# CurlingStoneSchematic.net
KiCad netlist of a schematic drawn in Altium Designer
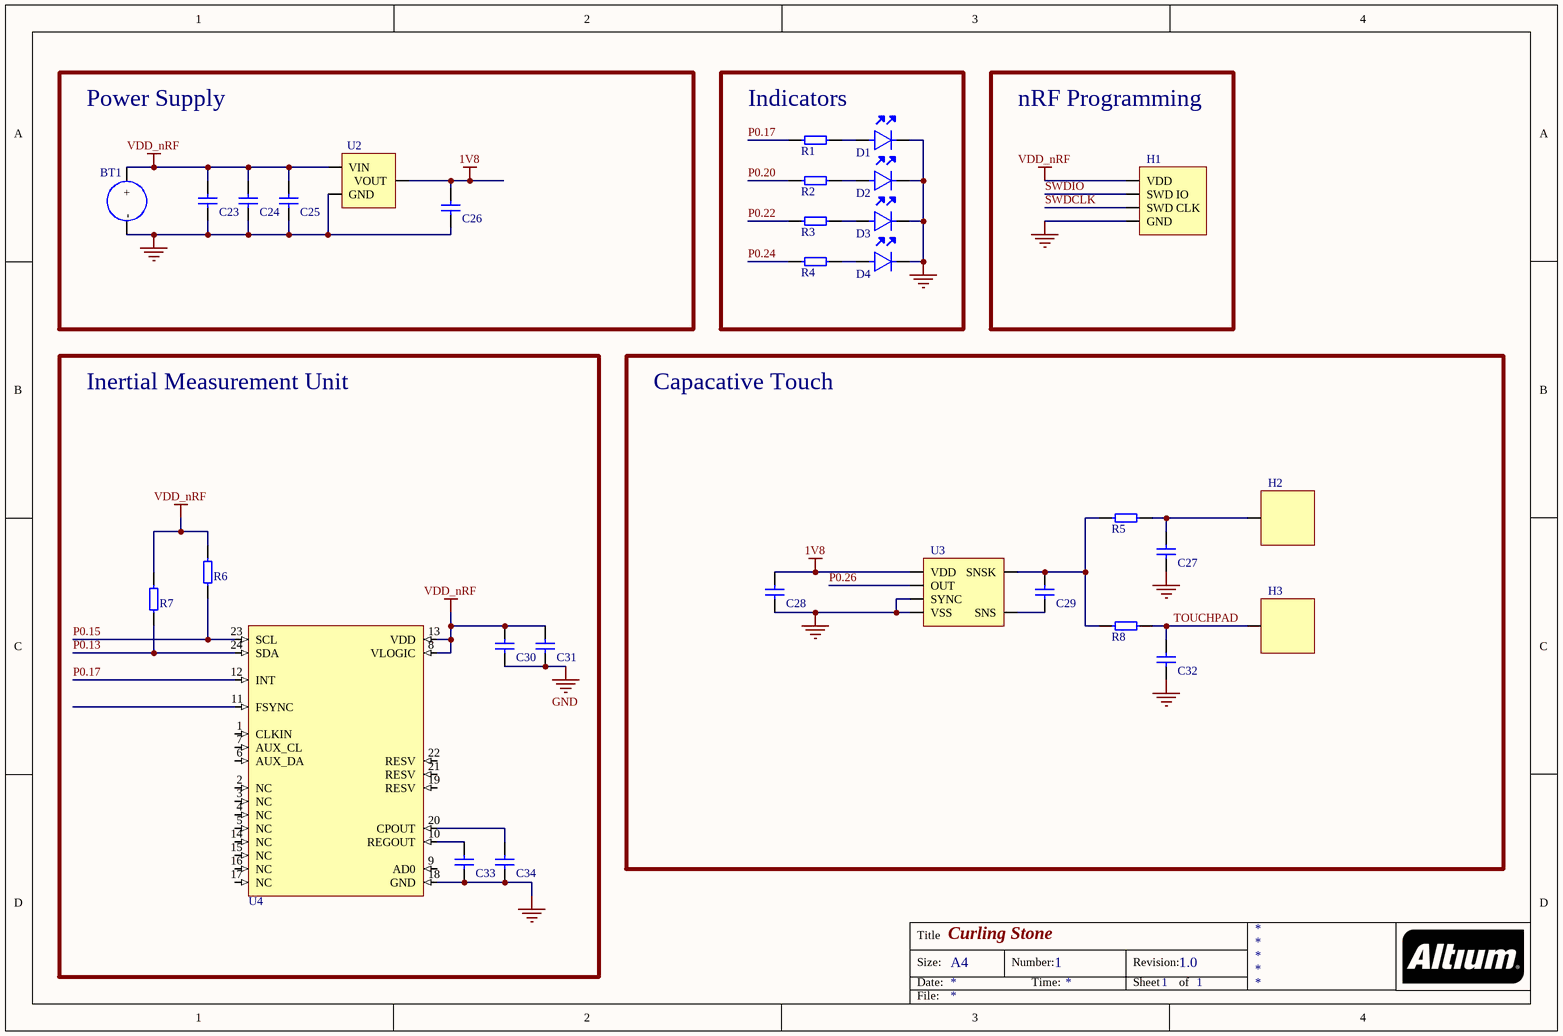
[diagram p0: CurlingStoneSchematic.SchDoc]

(export (version "E")
  (design (tool "Eeschema 10.0.6"))
  (components
    (comp (ref "BT1")
      (value "Battery Holder")
      (footprint "Battery Holder")
      (description "Battery Holder 1-Cell 20mm Size Tin Nickel SMT Mount T/R")
      (libsource (lib "ElsysSchematicLibrary") (part "Battery Holder"))
    )
    (comp (ref "C23")
      (value "0603 Capacitor")
      (footprint "0603")
      (libsource (lib "CurlingStoneSchematicLibrary") (part "0603 Capacitor"))
    )
    (comp (ref "C24")
      (value "0603 Capacitor")
      (footprint "0603")
      (libsource (lib "CurlingStoneSchematicLibrary") (part "0603 Capacitor"))
    )
    (comp (ref "C25")
      (value "0603 Capacitor")
      (footprint "0603")
      (libsource (lib "CurlingStoneSchematicLibrary") (part "0603 Capacitor"))
    )
    (comp (ref "C26")
      (value "0603 Capacitor")
      (footprint "0603")
      (libsource (lib "CurlingStoneSchematicLibrary") (part "0603 Capacitor"))
    )
    (comp (ref "C27")
      (value "0603 Capacitor")
      (footprint "0603")
      (libsource (lib "CurlingStoneSchematicLibrary") (part "0603 Capacitor"))
    )
    (comp (ref "C28")
      (value "0603 Capacitor")
      (footprint "0603")
      (libsource (lib "CurlingStoneSchematicLibrary") (part "0603 Capacitor"))
    )
    (comp (ref "C29")
      (value "0603 Capacitor")
      (footprint "0603")
      (libsource (lib "CurlingStoneSchematicLibrary") (part "0603 Capacitor"))
    )
    (comp (ref "C30")
      (value "0603 Capacitor")
      (footprint "0603")
      (libsource (lib "CurlingStoneSchematicLibrary") (part "0603 Capacitor"))
    )
    (comp (ref "C31")
      (value "0603 Capacitor")
      (footprint "0603")
      (libsource (lib "CurlingStoneSchematicLibrary") (part "0603 Capacitor"))
    )
    (comp (ref "C32")
      (value "0603 Capacitor")
      (footprint "0603")
      (libsource (lib "CurlingStoneSchematicLibrary") (part "0603 Capacitor"))
    )
    (comp (ref "C33")
      (value "0603 Capacitor")
      (footprint "0603")
      (libsource (lib "CurlingStoneSchematicLibrary") (part "0603 Capacitor"))
    )
    (comp (ref "C34")
      (value "0603 Capacitor")
      (footprint "0603")
      (libsource (lib "CurlingStoneSchematicLibrary") (part "0603 Capacitor"))
    )
    (comp (ref "D1")
      (value "0603 LED")
      (footprint "0603 LED")
      (description "LED Uni-Color Green 574nm 2-Pin Chip LED T/R")
      (libsource (lib "CurlingStoneSchematicLibrary") (part "0603 LED"))
    )
    (comp (ref "D2")
      (value "0603 LED")
      (footprint "0603 LED")
      (description "LED Uni-Color Green 574nm 2-Pin Chip LED T/R")
      (libsource (lib "CurlingStoneSchematicLibrary") (part "0603 LED"))
    )
    (comp (ref "D3")
      (value "0603 LED")
      (footprint "0603 LED")
      (description "LED Uni-Color Green 574nm 2-Pin Chip LED T/R")
      (libsource (lib "CurlingStoneSchematicLibrary") (part "0603 LED"))
    )
    (comp (ref "D4")
      (value "0603 LED")
      (footprint "0603 LED")
      (description "LED Uni-Color Green 574nm 2-Pin Chip LED T/R")
      (libsource (lib "CurlingStoneSchematicLibrary") (part "0603 LED"))
    )
    (comp (ref "H1")
      (value "4x1 Header")
      (footprint "4x1 HEADER TH")
      (libsource (lib "ElsysSchematicLibrary") (part "4x1 Header"))
    )
    (comp (ref "H2")
      (value "Electrode")
      (footprint "ELECTRODE EXTERNAL")
      (libsource (lib "CurlingStoneSchematicLibrary") (part "Electrode"))
    )
    (comp (ref "H3")
      (value "Electrode")
      (footprint "ELECTRODE INTERNAL")
      (libsource (lib "CurlingStoneSchematicLibrary") (part "Electrode"))
    )
    (comp (ref "R1")
      (value "0603 Resistor")
      (footprint "0603")
      (libsource (lib "CurlingStoneSchematicLibrary") (part "0603 Resistor"))
    )
    (comp (ref "R2")
      (value "0603 Resistor")
      (footprint "0603")
      (libsource (lib "CurlingStoneSchematicLibrary") (part "0603 Resistor"))
    )
    (comp (ref "R3")
      (value "0603 Resistor")
      (footprint "0603")
      (libsource (lib "CurlingStoneSchematicLibrary") (part "0603 Resistor"))
    )
    (comp (ref "R4")
      (value "0603 Resistor")
      (footprint "0603")
      (libsource (lib "CurlingStoneSchematicLibrary") (part "0603 Resistor"))
    )
    (comp (ref "R5")
      (value "0603 Resistor")
      (footprint "0603")
      (libsource (lib "CurlingStoneSchematicLibrary") (part "0603 Resistor"))
    )
    (comp (ref "R6")
      (value "0603 Resistor")
      (footprint "0603")
      (libsource (lib "CurlingStoneSchematicLibrary") (part "0603 Resistor"))
    )
    (comp (ref "R7")
      (value "0603 Resistor")
      (footprint "0603")
      (libsource (lib "CurlingStoneSchematicLibrary") (part "0603 Resistor"))
    )
    (comp (ref "R8")
      (value "0603 Resistor")
      (footprint "0603")
      (libsource (lib "CurlingStoneSchematicLibrary") (part "0603 Resistor"))
    )
    (comp (ref "U2")
      (value "MCP1700 1V8")
      (footprint "MCP1700 SOT-23")
      (libsource (lib "ElsysSchematicLibrary") (part "MCP1700 1V8"))
    )
    (comp (ref "U3")
      (value "Capacative Touch")
      (footprint "CAPACATIVE TOUCH")
      (description "Capacitive Touch Screen 1Keys 6-Pin SOT-23 Tape and Reel")
      (libsource (lib "CurlingStoneSchematicLibrary") (part "Capacative Touch"))
    )
    (comp (ref "U4")
      (value "MPU-6050")
      (footprint "MPU-6050")
      (description "INVENSENSE   MPU-6050   GYRO / ACCEL, 6-AXIS, I2C, QFN-24")
      (libsource (lib "CurlingStoneSchematicLibrary") (part "MPU-6050"))
    )
  )
  (nets
    (net (code "1") (name "/P0.13") (class "Default")
      (node (ref "R7") (pin "1") (pintype "passive"))
      (node (ref "U4") (pin "24") (pinfunction "SDA_24") (pintype "input"))
    )
    (net (code "2") (name "/P0.15") (class "Default")
      (node (ref "R6") (pin "1") (pintype "passive"))
      (node (ref "U4") (pin "23") (pinfunction "SCL_23") (pintype "input"))
    )
    (net (code "3") (name "/P0.17") (class "Default")
      (node (ref "R1") (pin "1") (pintype "passive"))
      (node (ref "U4") (pin "12") (pinfunction "INT_12") (pintype "input"))
    )
    (net (code "4") (name "/P0.20") (class "Default") (node (ref "R2") (pin "1") (pintype "passive")))
    (net (code "5") (name "/P0.22") (class "Default") (node (ref "R3") (pin "1") (pintype "passive")))
    (net (code "6") (name "/P0.24") (class "Default") (node (ref "R4") (pin "1") (pintype "passive")))
    (net (code "7") (name "/P0.26") (class "Default")
      (node (ref "U3") (pin "1") (pinfunction "OUT_1") (pintype "passive"))
    )
    (net (code "8") (name "/SWDCLK") (class "Default")
      (node (ref "H1") (pin "4") (pinfunction "SWD_CLK_4") (pintype "passive"))
    )
    (net (code "9") (name "/SWDIO") (class "Default")
      (node (ref "H1") (pin "3") (pinfunction "SWD_IO_3") (pintype "passive"))
    )
    (net (code "10") (name "/TOUCHPAD") (class "Default")
      (node (ref "C32") (pin "2") (pintype "passive"))
      (node (ref "H3") (pin "1") (pinfunction "GND_1") (pintype "passive"))
      (node (ref "R8") (pin "2") (pintype "passive"))
    )
    (net (code "11") (name "1V8") (class "Default")
      (node (ref "C26") (pin "2") (pintype "passive"))
      (node (ref "C28") (pin "2") (pintype "passive"))
      (node (ref "U2") (pin "2") (pinfunction "VOUT_2") (pintype "passive"))
      (node (ref "U3") (pin "5") (pinfunction "VDD_5") (pintype "passive"))
    )
    (net (code "12") (name "GND") (class "Default")
      (node (ref "BT1") (pin "2") (pinfunction "-_2") (pintype "passive"))
      (node (ref "C23") (pin "1") (pintype "passive"))
      (node (ref "C24") (pin "1") (pintype "passive"))
      (node (ref "C25") (pin "1") (pintype "passive"))
      (node (ref "C26") (pin "1") (pintype "passive"))
      (node (ref "C27") (pin "1") (pintype "passive"))
      (node (ref "C28") (pin "1") (pintype "passive"))
      (node (ref "C30") (pin "1") (pintype "passive"))
      (node (ref "C31") (pin "1") (pintype "passive"))
      (node (ref "C32") (pin "1") (pintype "passive"))
      (node (ref "C33") (pin "1") (pintype "passive"))
      (node (ref "C34") (pin "1") (pintype "passive"))
      (node (ref "D1") (pin "2") (pintype "passive"))
      (node (ref "D2") (pin "2") (pintype "passive"))
      (node (ref "D3") (pin "2") (pintype "passive"))
      (node (ref "D4") (pin "2") (pintype "passive"))
      (node (ref "H1") (pin "2") (pinfunction "GND_2") (pintype "passive"))
      (node (ref "U2") (pin "1") (pinfunction "GND_1") (pintype "passive"))
      (node (ref "U3") (pin "2") (pinfunction "VSS_2") (pintype "passive"))
      (node (ref "U3") (pin "6") (pinfunction "SYNC_6") (pintype "passive"))
      (node (ref "U4") (pin "18") (pinfunction "GND_18") (pintype "input"))
    )
    (net (code "13") (name "Net-(D1-Pad1)") (class "Default")
      (node (ref "D1") (pin "1") (pintype "passive"))
      (node (ref "R1") (pin "2") (pintype "passive"))
    )
    (net (code "14") (name "Net-(D2-Pad1)") (class "Default")
      (node (ref "D2") (pin "1") (pintype "passive"))
      (node (ref "R2") (pin "2") (pintype "passive"))
    )
    (net (code "15") (name "Net-(D3-Pad1)") (class "Default")
      (node (ref "D3") (pin "1") (pintype "passive"))
      (node (ref "R3") (pin "2") (pintype "passive"))
    )
    (net (code "16") (name "Net-(D4-Pad1)") (class "Default")
      (node (ref "D4") (pin "1") (pintype "passive"))
      (node (ref "R4") (pin "2") (pintype "passive"))
    )
    (net (code "17") (name "Net-(H2-GND)") (class "Default")
      (node (ref "C27") (pin "2") (pintype "passive"))
      (node (ref "H2") (pin "1") (pinfunction "GND_1") (pintype "passive"))
      (node (ref "R5") (pin "2") (pintype "passive"))
    )
    (net (code "18") (name "Net-(U3-SNS)") (class "Default")
      (node (ref "C29") (pin "1") (pintype "passive"))
      (node (ref "U3") (pin "4") (pinfunction "SNS_4") (pintype "passive"))
    )
    (net (code "19") (name "Net-(U3-SNSK)") (class "Default")
      (node (ref "C29") (pin "2") (pintype "passive"))
      (node (ref "R5") (pin "1") (pintype "passive"))
      (node (ref "R8") (pin "1") (pintype "passive"))
      (node (ref "U3") (pin "3") (pinfunction "SNSK_3") (pintype "passive"))
    )
    (net (code "20") (name "Net-(U4-CPOUT)") (class "Default")
      (node (ref "C34") (pin "2") (pintype "passive"))
      (node (ref "U4") (pin "20") (pinfunction "CPOUT_20") (pintype "input"))
    )
    (net (code "21") (name "Net-(U4-REGOUT)") (class "Default")
      (node (ref "C33") (pin "2") (pintype "passive"))
      (node (ref "U4") (pin "10") (pinfunction "REGOUT_10") (pintype "input"))
    )
    (net (code "22") (name "VDD_nRF") (class "Default")
      (node (ref "BT1") (pin "1") (pinfunction "+_1") (pintype "passive"))
      (node (ref "C23") (pin "2") (pintype "passive"))
      (node (ref "C24") (pin "2") (pintype "passive"))
      (node (ref "C25") (pin "2") (pintype "passive"))
      (node (ref "C30") (pin "2") (pintype "passive"))
      (node (ref "C31") (pin "2") (pintype "passive"))
      (node (ref "H1") (pin "1") (pinfunction "VDD_1") (pintype "passive"))
      (node (ref "R6") (pin "2") (pintype "passive"))
      (node (ref "R7") (pin "2") (pintype "passive"))
      (node (ref "U2") (pin "3") (pinfunction "VIN_3") (pintype "passive"))
      (node (ref "U4") (pin "13") (pinfunction "VDD_13") (pintype "input"))
      (node (ref "U4") (pin "8") (pinfunction "VLOGIC_8") (pintype "input"))
    )
    (net (code "23") (name "unconnected-(U4-AD0-Pad9)") (class "Default")
      (node (ref "U4") (pin "9") (pinfunction "AD0_9") (pintype "input"))
    )
    (net (code "24") (name "unconnected-(U4-AUX_CL-Pad7)") (class "Default")
      (node (ref "U4") (pin "7") (pinfunction "AUX_CL_7") (pintype "input"))
    )
    (net (code "25") (name "unconnected-(U4-AUX_DA-Pad6)") (class "Default")
      (node (ref "U4") (pin "6") (pinfunction "AUX_DA_6") (pintype "input"))
    )
    (net (code "26") (name "unconnected-(U4-CLKIN-Pad1)") (class "Default")
      (node (ref "U4") (pin "1") (pinfunction "CLKIN_1") (pintype "input"))
    )
    (net (code "27") (name "unconnected-(U4-FSYNC-Pad11)") (class "Default")
      (node (ref "U4") (pin "11") (pinfunction "FSYNC_11") (pintype "input"))
    )
    (net (code "28") (name "unconnected-(U4-NC-Pad2)") (class "Default")
      (node (ref "U4") (pin "2") (pinfunction "NC_2") (pintype "input"))
    )
    (net (code "29") (name "unconnected-(U4-NC-Pad3)") (class "Default")
      (node (ref "U4") (pin "3") (pinfunction "NC_3") (pintype "input"))
    )
    (net (code "30") (name "unconnected-(U4-NC-Pad4)") (class "Default")
      (node (ref "U4") (pin "4") (pinfunction "NC_4") (pintype "input"))
    )
    (net (code "31") (name "unconnected-(U4-NC-Pad5)") (class "Default")
      (node (ref "U4") (pin "5") (pinfunction "NC_5") (pintype "input"))
    )
    (net (code "32") (name "unconnected-(U4-NC-Pad14)") (class "Default")
      (node (ref "U4") (pin "14") (pinfunction "NC_14") (pintype "input"))
    )
    (net (code "33") (name "unconnected-(U4-NC-Pad15)") (class "Default")
      (node (ref "U4") (pin "15") (pinfunction "NC_15") (pintype "input"))
    )
    (net (code "34") (name "unconnected-(U4-NC-Pad16)") (class "Default")
      (node (ref "U4") (pin "16") (pinfunction "NC_16") (pintype "input"))
    )
    (net (code "35") (name "unconnected-(U4-NC-Pad17)") (class "Default")
      (node (ref "U4") (pin "17") (pinfunction "NC_17") (pintype "input"))
    )
    (net (code "36") (name "unconnected-(U4-RESV-Pad19)") (class "Default")
      (node (ref "U4") (pin "19") (pinfunction "RESV_19") (pintype "input"))
    )
    (net (code "37") (name "unconnected-(U4-RESV-Pad21)") (class "Default")
      (node (ref "U4") (pin "21") (pinfunction "RESV_21") (pintype "input"))
    )
    (net (code "38") (name "unconnected-(U4-RESV-Pad22)") (class "Default")
      (node (ref "U4") (pin "22") (pinfunction "RESV_22") (pintype "input"))
    )
  )
)
